# TestBoard.net
KiCad netlist of a schematic drawn in EAGLE
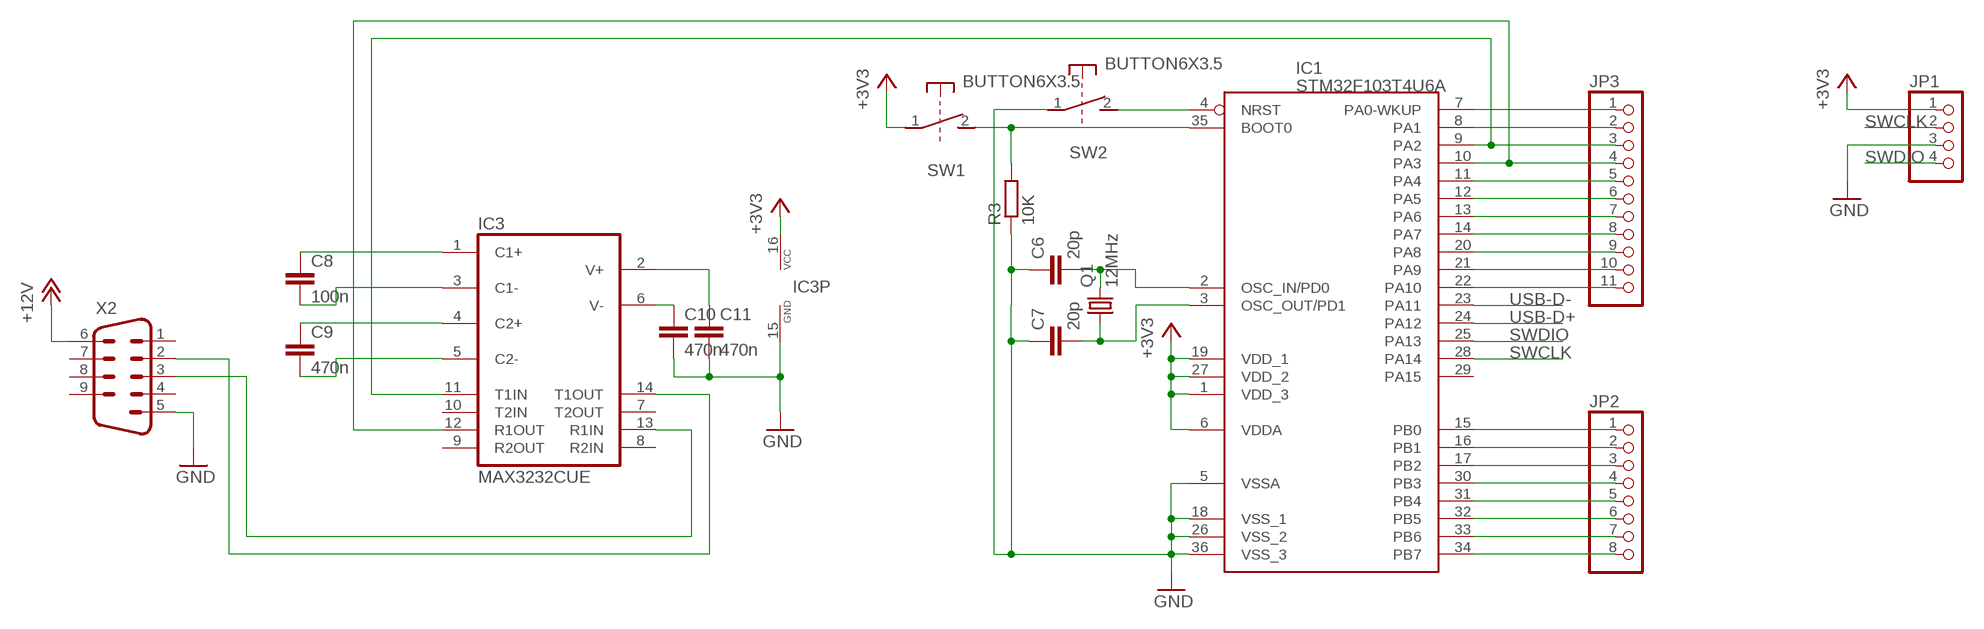
[diagram p0: schematic, sheet 1]
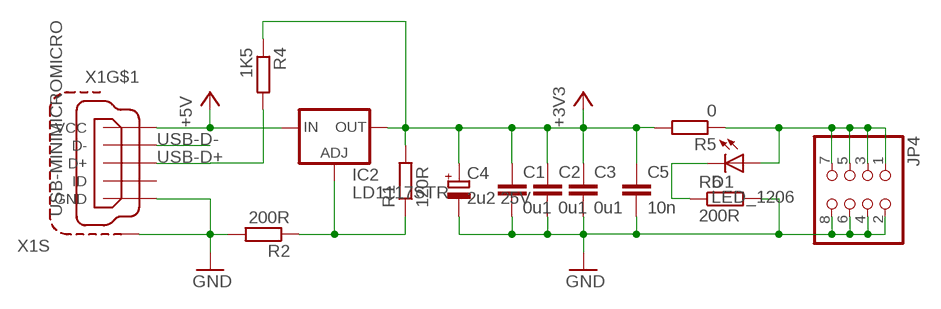
[diagram p1: schematic, sheet 2]

(export (version "E")
  (design (tool "Eeschema 10.0.6"))
  (components
    (comp (ref "C6")
      (value "20p")
      (footprint "eagle-import:CAP0805")
      (libsource (lib "eagle-import") (part "CAP_0805"))
    )
    (comp (ref "C7")
      (value "20p")
      (footprint "eagle-import:CAP0805")
      (libsource (lib "eagle-import") (part "CAP_0805"))
    )
    (comp (ref "C8")
      (value "100n")
      (footprint "eagle-import:CAP0805")
      (libsource (lib "eagle-import") (part "CAP_0805"))
    )
    (comp (ref "C9")
      (value "470n")
      (footprint "eagle-import:CAP0805")
      (libsource (lib "eagle-import") (part "CAP_0805"))
    )
    (comp (ref "C10")
      (value "470n")
      (footprint "eagle-import:CAP0805")
      (libsource (lib "eagle-import") (part "CAP_0805"))
    )
    (comp (ref "C11")
      (value "470n")
      (footprint "eagle-import:CAP0805")
      (libsource (lib "eagle-import") (part "CAP_0805"))
    )
    (comp (ref "IC1")
      (value "STM32F103T4U6A")
      (footprint "eagle-import:QFN50P606X606X100-36")
      (libsource (lib "eagle-import") (part "STM32F103T4U6A"))
    )
    (comp (ref "IC3")
      (value "MAX3232CUE")
      (footprint "eagle-import:TSSOP16")
      (fields (field (name "MF") "MAXIM") (field (name "MPN") "MAX3232CUE+"))
      (libsource (lib "eagle-import") (part "MAX3232UEC"))
    )
    (comp (ref "JP1")
      (value "PINHD-1X4")
      (footprint "eagle-import:1X04")
      (libsource (lib "eagle-import") (part "PINHD-1X4"))
    )
    (comp (ref "JP2")
      (value "PINHD-1X8")
      (footprint "eagle-import:1X08")
      (libsource (lib "eagle-import") (part "PINHD-1X8"))
    )
    (comp (ref "JP3")
      (value "PINHD-1X11")
      (footprint "eagle-import:1X11")
      (libsource (lib "eagle-import") (part "PINHD-1X11"))
    )
    (comp (ref "Q1")
      (value "12MHz")
      (footprint "eagle-import:HC49UP")
      (libsource (lib "eagle-import") (part "CRYSTALHC49UP"))
    )
    (comp (ref "R3")
      (value "10K")
      (footprint "eagle-import:RESC2012X50")
      (libsource (lib "eagle-import") (part "R_R0805"))
    )
    (comp (ref "SW1")
      (value "BUTTON6X3.5")
      (footprint "eagle-import:SW-6X3.5")
      (libsource (lib "eagle-import") (part "BUTTON6X3.5"))
    )
    (comp (ref "SW2")
      (value "BUTTON6X3.5")
      (footprint "eagle-import:SW-6X3.5")
      (libsource (lib "eagle-import") (part "BUTTON6X3.5"))
    )
    (comp (ref "X2")
      (value "M09-182")
      (footprint "eagle-import:182-009-MALE")
      (libsource (lib "eagle-import") (part "M09-182"))
    )
    (comp (ref "C1")
      (value "0u1")
      (footprint "eagle-import:CAP0805")
      (libsource (lib "eagle-import") (part "CAP_0805"))
    )
    (comp (ref "C2")
      (value "0u1")
      (footprint "eagle-import:CAP0805")
      (libsource (lib "eagle-import") (part "CAP_0805"))
    )
    (comp (ref "C3")
      (value "0u1")
      (footprint "eagle-import:CAP0805")
      (libsource (lib "eagle-import") (part "CAP_0805"))
    )
    (comp (ref "C4")
      (value "2u2 25V")
      (footprint "eagle-import:CAPMP3317X180")
      (libsource (lib "eagle-import") (part "CAP-POL_CAPE3216-A"))
    )
    (comp (ref "C5")
      (value "10n")
      (footprint "eagle-import:CAP0805")
      (libsource (lib "eagle-import") (part "CAP_0805"))
    )
    (comp (ref "D1")
      (value "LED_1206")
      (footprint "eagle-import:LED1206")
      (libsource (lib "eagle-import") (part "LED_1206"))
    )
    (comp (ref "IC2")
      (value "LD1117STR")
      (footprint "eagle-import:SOT230P700X180-4")
      (libsource (lib "eagle-import") (part "VREG-ADJLD1117S"))
    )
    (comp (ref "JP4")
      (value "PINHD-2X4")
      (footprint "eagle-import:2X04")
      (libsource (lib "eagle-import") (part "PINHD-2X4"))
    )
    (comp (ref "R1")
      (value "120R")
      (footprint "eagle-import:RESC2012X50")
      (libsource (lib "eagle-import") (part "R_R0805"))
    )
    (comp (ref "R2")
      (value "200R")
      (footprint "eagle-import:RESC2012X50")
      (libsource (lib "eagle-import") (part "R_R0805"))
    )
    (comp (ref "R4")
      (value "1K5")
      (footprint "eagle-import:RESC2012X50")
      (libsource (lib "eagle-import") (part "R_R0805"))
    )
    (comp (ref "R5")
      (value "0")
      (footprint "eagle-import:RESC2012X50")
      (libsource (lib "eagle-import") (part "R_R0805"))
    )
    (comp (ref "R6")
      (value "200R")
      (footprint "eagle-import:RESC2012X50")
      (libsource (lib "eagle-import") (part "R_R0805"))
    )
    (comp (ref "X1")
      (value "USB-MINIMICROMICRO")
      (footprint "eagle-import:USB-B-MICRO-SMD")
      (libsource (lib "eagle-import") (part "USB-MINIMICROMICRO"))
    )
  )
  (nets
    (net (code "1") (name "+3V3") (class "Default")
      (node (ref "C1") (pin "1") (pinfunction "1_1") (pintype "passive"))
      (node (ref "C2") (pin "1") (pinfunction "1_1") (pintype "passive"))
      (node (ref "C3") (pin "1") (pinfunction "1_1") (pintype "passive"))
      (node (ref "C4") (pin "1") (pinfunction "+_1") (pintype "passive"))
      (node (ref "C5") (pin "1") (pinfunction "1_1") (pintype "passive"))
      (node (ref "IC1") (pin "1") (pinfunction "VDD_3_1") (pintype "power_in"))
      (node (ref "IC1") (pin "19") (pinfunction "VDD_1_19") (pintype "power_in"))
      (node (ref "IC1") (pin "27") (pinfunction "VDD_2_27") (pintype "power_in"))
      (node (ref "IC1") (pin "6") (pinfunction "VDDA_6") (pintype "power_in"))
      (node (ref "IC2") (pin "2") (pinfunction "OUT_2") (pintype "passive"))
      (node (ref "IC2") (pin "4") (pinfunction "OUT_4") (pintype "passive"))
      (node (ref "IC3") (pin "16") (pinfunction "VCC_16") (pintype "power_in"))
      (node (ref "JP1") (pin "1") (pinfunction "1_1") (pintype "passive"))
      (node (ref "R1") (pin "2") (pinfunction "2_2") (pintype "passive"))
      (node (ref "R4") (pin "1") (pinfunction "1_1") (pintype "passive"))
      (node (ref "R5") (pin "2") (pinfunction "2_2") (pintype "passive"))
      (node (ref "SW1") (pin "1") (pinfunction "1_1") (pintype "passive"))
    )
    (net (code "2") (name "+5V") (class "Default")
      (node (ref "IC2") (pin "3") (pinfunction "IN_3") (pintype "input"))
      (node (ref "X1") (pin "VBUS") (pinfunction "VCC_VBUS") (pintype "passive"))
    )
    (net (code "3") (name "+12V") (class "Default")
      (node (ref "X2") (pin "6") (pinfunction "6_6") (pintype "passive"))
    )
    (net (code "4") (name "GND") (class "Default")
      (node (ref "C1") (pin "2") (pinfunction "2_2") (pintype "passive"))
      (node (ref "C10") (pin "2") (pinfunction "2_2") (pintype "passive"))
      (node (ref "C11") (pin "2") (pinfunction "2_2") (pintype "passive"))
      (node (ref "C2") (pin "2") (pinfunction "2_2") (pintype "passive"))
      (node (ref "C3") (pin "2") (pinfunction "2_2") (pintype "passive"))
      (node (ref "C4") (pin "2") (pinfunction "-_2") (pintype "passive"))
      (node (ref "C5") (pin "2") (pinfunction "2_2") (pintype "passive"))
      (node (ref "C6") (pin "1") (pinfunction "1_1") (pintype "passive"))
      (node (ref "C7") (pin "1") (pinfunction "1_1") (pintype "passive"))
      (node (ref "IC1") (pin "18") (pinfunction "VSS_1_18") (pintype "power_in"))
      (node (ref "IC1") (pin "26") (pinfunction "VSS_2_26") (pintype "power_in"))
      (node (ref "IC1") (pin "36") (pinfunction "VSS_3_36") (pintype "power_in"))
      (node (ref "IC1") (pin "5") (pinfunction "VSSA_5") (pintype "power_in"))
      (node (ref "IC3") (pin "15") (pinfunction "GND_15") (pintype "power_in"))
      (node (ref "JP1") (pin "3") (pinfunction "3_3") (pintype "passive"))
      (node (ref "JP4") (pin "2") (pinfunction "2_2") (pintype "passive"))
      (node (ref "JP4") (pin "4") (pinfunction "4_4") (pintype "passive"))
      (node (ref "JP4") (pin "6") (pinfunction "6_6") (pintype "passive"))
      (node (ref "JP4") (pin "8") (pinfunction "8_8") (pintype "passive"))
      (node (ref "R2") (pin "2") (pinfunction "2_2") (pintype "passive"))
      (node (ref "R3") (pin "1") (pinfunction "1_1") (pintype "passive"))
      (node (ref "R6") (pin "2") (pinfunction "2_2") (pintype "passive"))
      (node (ref "SW2") (pin "1") (pinfunction "1_1") (pintype "passive"))
      (node (ref "X1") (pin "GND") (pinfunction "GND_GND") (pintype "passive"))
      (node (ref "X1") (pin "SHIELD1") (pinfunction "S1_SHIELD1") (pintype "passive"))
      (node (ref "X1") (pin "SHIELD2") (pinfunction "S1_SHIELD2") (pintype "passive"))
      (node (ref "X1") (pin "SHIELD3") (pinfunction "S1_SHIELD3") (pintype "passive"))
      (node (ref "X2") (pin "5") (pinfunction "5_5") (pintype "passive"))
    )
    (net (code "5") (name "Net-(D1-PadA)") (class "Default")
      (node (ref "D1") (pin "A") (pinfunction "A_A") (pintype "passive"))
      (node (ref "JP4") (pin "1") (pinfunction "1_1") (pintype "passive"))
      (node (ref "JP4") (pin "3") (pinfunction "3_3") (pintype "passive"))
      (node (ref "JP4") (pin "5") (pinfunction "5_5") (pintype "passive"))
      (node (ref "JP4") (pin "7") (pinfunction "7_7") (pintype "passive"))
      (node (ref "R5") (pin "1") (pinfunction "1_1") (pintype "passive"))
    )
    (net (code "6") (name "Net-(D1-PadC)") (class "Default")
      (node (ref "D1") (pin "C") (pinfunction "C_C") (pintype "passive"))
      (node (ref "R6") (pin "1") (pinfunction "1_1") (pintype "passive"))
    )
    (net (code "7") (name "Net-(IC1-BOOT0)") (class "Default")
      (node (ref "IC1") (pin "35") (pinfunction "BOOT0_35") (pintype "bidirectional"))
      (node (ref "R3") (pin "2") (pinfunction "2_2") (pintype "passive"))
      (node (ref "SW1") (pin "2") (pinfunction "2_2") (pintype "passive"))
    )
    (net (code "8") (name "Net-(IC1-NRST)") (class "Default")
      (node (ref "IC1") (pin "4") (pinfunction "NRST_4") (pintype "bidirectional"))
      (node (ref "SW2") (pin "2") (pinfunction "2_2") (pintype "passive"))
    )
    (net (code "9") (name "Net-(IC1-OSC_IN{slash}PD0)") (class "Default")
      (node (ref "C6") (pin "2") (pinfunction "2_2") (pintype "passive"))
      (node (ref "IC1") (pin "2") (pinfunction "OSC_IN/PD0_2") (pintype "bidirectional"))
      (node (ref "Q1") (pin "2") (pinfunction "2_2") (pintype "passive"))
    )
    (net (code "10") (name "Net-(IC1-OSC_OUT{slash}PD1)") (class "Default")
      (node (ref "C7") (pin "2") (pinfunction "2_2") (pintype "passive"))
      (node (ref "IC1") (pin "3") (pinfunction "OSC_OUT/PD1_3") (pintype "bidirectional"))
      (node (ref "Q1") (pin "1") (pinfunction "1_1") (pintype "passive"))
    )
    (net (code "11") (name "Net-(IC1-PA0-WKUP)") (class "Default")
      (node (ref "IC1") (pin "7") (pinfunction "PA0-WKUP_7") (pintype "bidirectional"))
      (node (ref "JP3") (pin "1") (pinfunction "1_1") (pintype "passive"))
    )
    (net (code "12") (name "Net-(IC1-PA1)") (class "Default")
      (node (ref "IC1") (pin "8") (pinfunction "PA1_8") (pintype "bidirectional"))
      (node (ref "JP3") (pin "2") (pinfunction "2_2") (pintype "passive"))
    )
    (net (code "13") (name "Net-(IC1-PA2)") (class "Default")
      (node (ref "IC1") (pin "9") (pinfunction "PA2_9") (pintype "bidirectional"))
      (node (ref "IC3") (pin "11") (pinfunction "T1IN_11") (pintype "input"))
      (node (ref "JP3") (pin "3") (pinfunction "3_3") (pintype "passive"))
    )
    (net (code "14") (name "Net-(IC1-PA3)") (class "Default")
      (node (ref "IC1") (pin "10") (pinfunction "PA3_10") (pintype "bidirectional"))
      (node (ref "IC3") (pin "12") (pinfunction "R1OUT_12") (pintype "output"))
      (node (ref "JP3") (pin "4") (pinfunction "4_4") (pintype "passive"))
    )
    (net (code "15") (name "Net-(IC1-PA4)") (class "Default")
      (node (ref "IC1") (pin "11") (pinfunction "PA4_11") (pintype "bidirectional"))
      (node (ref "JP3") (pin "5") (pinfunction "5_5") (pintype "passive"))
    )
    (net (code "16") (name "Net-(IC1-PA5)") (class "Default")
      (node (ref "IC1") (pin "12") (pinfunction "PA5_12") (pintype "bidirectional"))
      (node (ref "JP3") (pin "6") (pinfunction "6_6") (pintype "passive"))
    )
    (net (code "17") (name "Net-(IC1-PA6)") (class "Default")
      (node (ref "IC1") (pin "13") (pinfunction "PA6_13") (pintype "bidirectional"))
      (node (ref "JP3") (pin "7") (pinfunction "7_7") (pintype "passive"))
    )
    (net (code "18") (name "Net-(IC1-PA7)") (class "Default")
      (node (ref "IC1") (pin "14") (pinfunction "PA7_14") (pintype "bidirectional"))
      (node (ref "JP3") (pin "8") (pinfunction "8_8") (pintype "passive"))
    )
    (net (code "19") (name "Net-(IC1-PA8)") (class "Default")
      (node (ref "IC1") (pin "20") (pinfunction "PA8_20") (pintype "bidirectional"))
      (node (ref "JP3") (pin "9") (pinfunction "9_9") (pintype "passive"))
    )
    (net (code "20") (name "Net-(IC1-PA9)") (class "Default")
      (node (ref "IC1") (pin "21") (pinfunction "PA9_21") (pintype "bidirectional"))
      (node (ref "JP3") (pin "10") (pinfunction "10_10") (pintype "passive"))
    )
    (net (code "21") (name "Net-(IC1-PA10)") (class "Default")
      (node (ref "IC1") (pin "22") (pinfunction "PA10_22") (pintype "bidirectional"))
      (node (ref "JP3") (pin "11") (pinfunction "11_11") (pintype "passive"))
    )
    (net (code "22") (name "Net-(IC1-PB0)") (class "Default")
      (node (ref "IC1") (pin "15") (pinfunction "PB0_15") (pintype "bidirectional"))
      (node (ref "JP2") (pin "1") (pinfunction "1_1") (pintype "passive"))
    )
    (net (code "23") (name "Net-(IC1-PB1)") (class "Default")
      (node (ref "IC1") (pin "16") (pinfunction "PB1_16") (pintype "bidirectional"))
      (node (ref "JP2") (pin "2") (pinfunction "2_2") (pintype "passive"))
    )
    (net (code "24") (name "Net-(IC1-PB2)") (class "Default")
      (node (ref "IC1") (pin "17") (pinfunction "PB2_17") (pintype "bidirectional"))
      (node (ref "JP2") (pin "3") (pinfunction "3_3") (pintype "passive"))
    )
    (net (code "25") (name "Net-(IC1-PB3)") (class "Default")
      (node (ref "IC1") (pin "30") (pinfunction "PB3_30") (pintype "bidirectional"))
      (node (ref "JP2") (pin "4") (pinfunction "4_4") (pintype "passive"))
    )
    (net (code "26") (name "Net-(IC1-PB4)") (class "Default")
      (node (ref "IC1") (pin "31") (pinfunction "PB4_31") (pintype "bidirectional"))
      (node (ref "JP2") (pin "5") (pinfunction "5_5") (pintype "passive"))
    )
    (net (code "27") (name "Net-(IC1-PB5)") (class "Default")
      (node (ref "IC1") (pin "32") (pinfunction "PB5_32") (pintype "bidirectional"))
      (node (ref "JP2") (pin "6") (pinfunction "6_6") (pintype "passive"))
    )
    (net (code "28") (name "Net-(IC1-PB6)") (class "Default")
      (node (ref "IC1") (pin "33") (pinfunction "PB6_33") (pintype "bidirectional"))
      (node (ref "JP2") (pin "7") (pinfunction "7_7") (pintype "passive"))
    )
    (net (code "29") (name "Net-(IC1-PB7)") (class "Default")
      (node (ref "IC1") (pin "34") (pinfunction "PB7_34") (pintype "bidirectional"))
      (node (ref "JP2") (pin "8") (pinfunction "8_8") (pintype "passive"))
    )
    (net (code "30") (name "Net-(IC2-ADJ)") (class "Default")
      (node (ref "IC2") (pin "1") (pinfunction "ADJ_1") (pintype "input"))
      (node (ref "R1") (pin "1") (pinfunction "1_1") (pintype "passive"))
      (node (ref "R2") (pin "1") (pinfunction "1_1") (pintype "passive"))
    )
    (net (code "31") (name "Net-(IC3A-C1+)") (class "Default")
      (node (ref "C8") (pin "1") (pinfunction "1_1") (pintype "passive"))
      (node (ref "IC3") (pin "1") (pinfunction "C1+_1") (pintype "bidirectional"))
    )
    (net (code "32") (name "Net-(IC3A-C1-)") (class "Default")
      (node (ref "C8") (pin "2") (pinfunction "2_2") (pintype "passive"))
      (node (ref "IC3") (pin "3") (pinfunction "C1-_3") (pintype "bidirectional"))
    )
    (net (code "33") (name "Net-(IC3A-C2+)") (class "Default")
      (node (ref "C9") (pin "1") (pinfunction "1_1") (pintype "passive"))
      (node (ref "IC3") (pin "4") (pinfunction "C2+_4") (pintype "bidirectional"))
    )
    (net (code "34") (name "Net-(IC3A-C2-)") (class "Default")
      (node (ref "C9") (pin "2") (pinfunction "2_2") (pintype "passive"))
      (node (ref "IC3") (pin "5") (pinfunction "C2-_5") (pintype "bidirectional"))
    )
    (net (code "35") (name "Net-(IC3A-R1IN)") (class "Default")
      (node (ref "IC3") (pin "13") (pinfunction "R1IN_13") (pintype "input"))
      (node (ref "X2") (pin "3") (pinfunction "3_3") (pintype "passive"))
    )
    (net (code "36") (name "Net-(IC3A-T1OUT)") (class "Default")
      (node (ref "IC3") (pin "14") (pinfunction "T1OUT_14") (pintype "output"))
      (node (ref "X2") (pin "2") (pinfunction "2_2") (pintype "passive"))
    )
    (net (code "37") (name "Net-(IC3A-V+)") (class "Default")
      (node (ref "C11") (pin "1") (pinfunction "1_1") (pintype "passive"))
      (node (ref "IC3") (pin "2") (pinfunction "V+_2") (pintype "bidirectional"))
    )
    (net (code "38") (name "Net-(IC3A-V-)") (class "Default")
      (node (ref "C10") (pin "1") (pinfunction "1_1") (pintype "passive"))
      (node (ref "IC3") (pin "6") (pinfunction "V-_6") (pintype "bidirectional"))
    )
    (net (code "39") (name "SWCLK") (class "Default")
      (node (ref "IC1") (pin "28") (pinfunction "PA14_28") (pintype "bidirectional"))
      (node (ref "JP1") (pin "2") (pinfunction "2_2") (pintype "passive"))
    )
    (net (code "40") (name "SWDIO") (class "Default")
      (node (ref "IC1") (pin "25") (pinfunction "PA13_25") (pintype "bidirectional"))
      (node (ref "JP1") (pin "4") (pinfunction "4_4") (pintype "passive"))
    )
    (net (code "41") (name "USB-D+") (class "Default")
      (node (ref "IC1") (pin "24") (pinfunction "PA12_24") (pintype "bidirectional"))
      (node (ref "R4") (pin "2") (pinfunction "2_2") (pintype "passive"))
      (node (ref "X1") (pin "D+") (pinfunction "D+_D+") (pintype "passive"))
    )
    (net (code "42") (name "USB-D-") (class "Default")
      (node (ref "IC1") (pin "23") (pinfunction "PA11_23") (pintype "bidirectional"))
      (node (ref "X1") (pin "D-") (pinfunction "D-_D-") (pintype "passive"))
    )
    (net (code "43") (name "unconnected-(IC1-PA15-Pad29)") (class "Default")
      (node (ref "IC1") (pin "29") (pinfunction "PA15_29") (pintype "bidirectional"))
    )
    (net (code "44") (name "unconnected-(IC3A-R2IN-Pad8)") (class "Default")
      (node (ref "IC3") (pin "8") (pinfunction "R2IN_8") (pintype "input"))
    )
    (net (code "45") (name "unconnected-(IC3A-R2OUT-Pad9)") (class "Default")
      (node (ref "IC3") (pin "9") (pinfunction "R2OUT_9") (pintype "output"))
    )
    (net (code "46") (name "unconnected-(IC3A-T2IN-Pad10)") (class "Default")
      (node (ref "IC3") (pin "10") (pinfunction "T2IN_10") (pintype "input"))
    )
    (net (code "47") (name "unconnected-(IC3A-T2OUT-Pad7)") (class "Default")
      (node (ref "IC3") (pin "7") (pinfunction "T2OUT_7") (pintype "output"))
    )
    (net (code "48") (name "unconnected-(X1-PadID)") (class "Default")
      (node (ref "X1") (pin "ID") (pinfunction "ID_ID") (pintype "passive"))
    )
    (net (code "49") (name "unconnected-(X2-Pad1)") (class "Default")
      (node (ref "X2") (pin "1") (pinfunction "1_1") (pintype "passive"))
    )
    (net (code "50") (name "unconnected-(X2-Pad4)") (class "Default")
      (node (ref "X2") (pin "4") (pinfunction "4_4") (pintype "passive"))
    )
    (net (code "51") (name "unconnected-(X2-Pad7)") (class "Default")
      (node (ref "X2") (pin "7") (pinfunction "7_7") (pintype "passive"))
    )
    (net (code "52") (name "unconnected-(X2-Pad8)") (class "Default")
      (node (ref "X2") (pin "8") (pinfunction "8_8") (pintype "passive"))
    )
    (net (code "53") (name "unconnected-(X2-Pad9)") (class "Default")
      (node (ref "X2") (pin "9") (pinfunction "9_9") (pintype "passive"))
    )
  )
)
